# JacdacRotary_26.net
KiCad netlist of a schematic drawn in Altium Designer
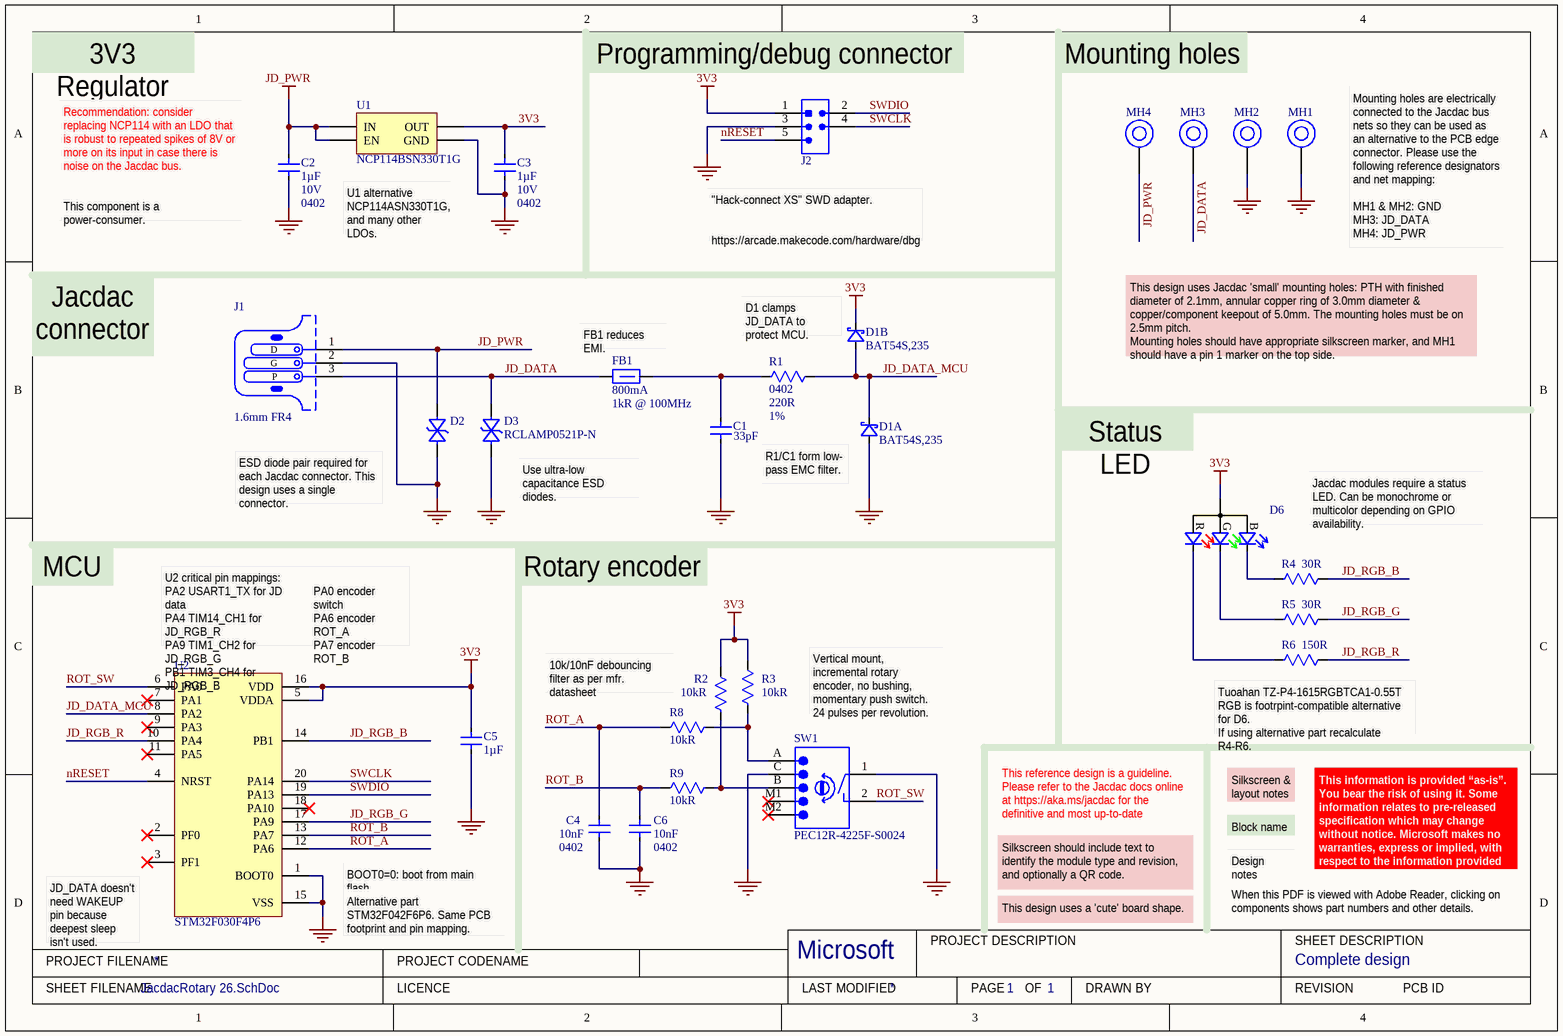
[diagram p0: JacdacRotary 26.SchDoc]

(export (version "E")
  (design (tool "Eeschema 10.0.6"))
  (components
    (comp (ref "C1")
      (value "CL05C330JB5NNNC")
      (footprint "C0402_0.55MM - without outline")
      (description "CAP CER 33PF 50V C0G/NP0 0402")
      (fields
        (field (name "MANUFACTURER") "Samsung")
        (field (name "TOLERANCE") "5%")
        (field (name "CAPACITANCE") "33pF")
      )
      (libsource (lib "Samsung") (part "CL05C330JB5NNNC"))
    )
    (comp (ref "C2")
      (value "CL05A105KP5NNNC")
      (footprint "C0402_0.55MM - without outline")
      (description "CAP CER 1UF 10V X5R 0402")
      (fields
        (field (name "MANUFACTURER") "Samsung")
        (field (name "TOLERANCE") "10%")
        (field (name "CAPACITANCE") "1µF")
        (field (name "VOLTAGE RATING") "10V")
        (field (name "CASE CODE (IMPERIAL)") "0402")
        (field (name "CREATED") "DG")
        (field (name "CHECKED") "?")
      )
      (libsource (lib "Samsung") (part "CL05A105KP5NNNC"))
    )
    (comp (ref "C3")
      (value "CL05A105KP5NNNC")
      (footprint "C0402_0.55MM - without outline")
      (description "CAP CER 1UF 10V X5R 0402")
      (fields
        (field (name "MANUFACTURER") "Samsung")
        (field (name "TOLERANCE") "10%")
        (field (name "CAPACITANCE") "1µF")
        (field (name "VOLTAGE RATING") "10V")
        (field (name "CASE CODE (IMPERIAL)") "0402")
        (field (name "CREATED") "DG")
        (field (name "CHECKED") "?")
      )
      (libsource (lib "Samsung") (part "CL05A105KP5NNNC"))
    )
    (comp (ref "C4")
      (value "~")
      (footprint "C0402_0.55MM - without outline")
      (description "CAP CER 10000PF 16V X7R 0402")
      (fields
        (field (name "MANUFACTURER") "Samsung")
        (field (name "MANUFACTURER PART NUMBER") "CL05B103JO5NNNC")
        (field (name "CAPACITANCE") "10nF")
        (field (name "CASE CODE (IMPERIAL)") "0402")
        (field (name "CREATED BY") "D. Gakure")
        (field (name "CHECKED BY") "?")
      )
      (libsource (lib "Samsung") (part "CL05B103JO5NNNC"))
    )
    (comp (ref "C5")
      (value "CL05A105KP5NNNC")
      (footprint "C0402_0.55MM - without outline")
      (description "CAP CER 1UF 10V X5R 0402")
      (fields
        (field (name "MANUFACTURER") "Samsung")
        (field (name "TOLERANCE") "10%")
        (field (name "CAPACITANCE") "1µF")
        (field (name "CREATED") "DG")
        (field (name "CHECKED") "?")
      )
      (libsource (lib "Samsung") (part "CL05A105KP5NNNC"))
    )
    (comp (ref "C6")
      (value "~")
      (footprint "C0402_0.55MM - without outline")
      (description "CAP CER 10000PF 16V X7R 0402")
      (fields
        (field (name "MANUFACTURER") "Samsung")
        (field (name "MANUFACTURER PART NUMBER") "CL05B103JO5NNNC")
        (field (name "CAPACITANCE") "10nF")
        (field (name "CASE CODE (IMPERIAL)") "0402")
        (field (name "CREATED BY") "D. Gakure")
        (field (name "CHECKED BY") "?")
      )
      (libsource (lib "Samsung") (part "CL05B103JO5NNNC"))
    )
    (comp (ref "D1")
      (value "BAT54S")
      (footprint "NXP-BAT54S-TO-236AB - without outline")
      (description "DIODE ARRAY SCHOTTKY 30V SOT23")
      (fields (field (name "MANUFACTURER") "Nexperia") (field (name "MANUFACTURER PART NUMBER") "BAT54S,235"))
      (libsource (lib "NXP") (part "BAT54S"))
    )
    (comp (ref "D2")
      (value "RCLAMP0521P-N")
      (footprint "TVS 0402 - L")
      (description "Bidirectional 5V (Max) 6V 16V 3.5A (8/20us) 0402 TVS RoHS")
      (fields
        (field (name "MANUFACTURER") "Born Semiconductor")
        (field (name "CREATED BY") "D Gakure")
        (field (name "CHECKED BY") "?")
      )
      (libsource (lib "BornSemiconductor") (part "RCLAMP0521P-N"))
    )
    (comp (ref "D3")
      (value "RCLAMP0521P-N")
      (footprint "TVS 0402 - L")
      (description "Bidirectional 5V (Max) 6V 16V 3.5A (8/20us) 0402 TVS RoHS")
      (fields
        (field (name "MANUFACTURER") "Born Semiconductor")
        (field (name "MANUFACTURER PART NUMBER") "RCLAMP0521P-N")
        (field (name "CREATED BY") "D Gakure")
        (field (name "CHECKED BY") "?")
      )
      (libsource (lib "BornSemiconductor") (part "RCLAMP0521P-N"))
    )
    (comp (ref "D6")
      (value "TZ-P4-1615RGBTCA1-0.55T")
      (footprint "TZ-P4-1615RGBTCA1-0.55T")
      (description "1615 Light Emitting Diodes (LED) RoHS")
      (fields
        (field (name "MANUFACTURER") "TUOZHAN")
        (field (name "CREATED BY") "D. Gakure")
        (field (name "CHECKED BY") "?")
      )
      (libsource (lib "Tuozhan") (part "TZ-P4-1615RGBTCA1-0.55T"))
    )
    (comp (ref "FB1")
      (value "TDK MPZ1608S102ATA00")
      (footprint "TDK MPZ1608 0.8mm - without outline")
      (description "0603 1k@100MHz 0.8A chip")
      (fields
        (field (name "TOLERANCE") "25%")
        (field (name "MANUFACTURER") "TDK")
        (field (name "CURRENT RATING") "800mA")
        (field (name "IMPEDANCE") "1kR @ 100MHz")
      )
      (libsource (lib "TDK") (part "TDK MPZ1608S102ATA00"))
    )
    (comp (ref "J1")
      (value "3 pin JACDAC edge connector")
      (footprint "JACDAC_EDGE_CONNECTOR_NO_TRACES")
      (description "3 pin Jacdac edge connector 1.27mm pitch")
      (fields
        (field (name "MANUFACTURER PART NUMBER") "JACDAC_EDGE_CONNECTOR")
        (field (name "PCB TYPE") "1.6mm FR4")
        (field (name "CHECKED BY") "?")
        (field (name "CREATED BY") "D. Gakure")
      )
      (libsource (lib "generic-con") (part "Jacdac edge connector"))
    )
    (comp (ref "J2")
      (value "Hack Connect Mini 1.27 mm pitch 2-row")
      (footprint "HACK_CONNECT_MINI_5_X_1_27")
      (libsource (lib "HackConnect") (part "HACK_CONNECT_MINI"))
    )
    (comp (ref "MH1")
      (value "MH_5.0MMK_3.0MMC_2.1MMD_PTH")
      (footprint "MH_5.0MMK_3.0MMC_2.1MMD_PTH:MH_5.0MMK_3.0MMC_2.1MMD_PTH")
      (description "Mounting Hole 5.0mm keepout, 3.0mm annualar ring and 2.1mm Drill PTH")
      (libsource (lib "generic") (part "MH_5.0MMK_3.0MMC_2.1MMD_PTH"))
    )
    (comp (ref "MH2")
      (value "MH_5.0MMK_3.0MMC_2.1MMD_PTH")
      (footprint "MH_5.0MMK_3.0MMC_2.1MMD_PTH:MH_5.0MMK_3.0MMC_2.1MMD_PTH")
      (description "Mounting Hole 5.0mm keepout, 3.0mm annualar ring and 2.1mm Drill PTH")
      (libsource (lib "generic") (part "MH_5.0MMK_3.0MMC_2.1MMD_PTH"))
    )
    (comp (ref "MH3")
      (value "MH_5.0MMK_3.0MMC_2.1MMD_PTH")
      (footprint "MH_5.0MMK_3.0MMC_2.1MMD_PTH:MH_5.0MMK_3.0MMC_2.1MMD_PTH")
      (description "Mounting Hole 5.0mm keepout, 3.0mm annualar ring and 2.1mm Drill PTH")
      (libsource (lib "generic") (part "MH_5.0MMK_3.0MMC_2.1MMD_PTH"))
    )
    (comp (ref "MH4")
      (value "MH_5.0MMK_3.0MMC_2.1MMD_PTH")
      (footprint "MH_5.0MMK_3.0MMC_2.1MMD_PTH:MH_5.0MMK_3.0MMC_2.1MMD_PTH")
      (description "Mounting Hole 5.0mm keepout, 3.0mm annualar ring and 2.1mm Drill PTH")
      (libsource (lib "generic") (part "MH_5.0MMK_3.0MMC_2.1MMD_PTH"))
    )
    (comp (ref "R1")
      (value "RC0402FR-07220RL")
      (footprint "R0402 - Without outline")
      (description "RES SMD 220 OHM 1% 1/16W 0402")
      (fields
        (field (name "MANUFACTURER") "Yageo")
        (field (name "CASE CODE (IMPERIAL)") "0402")
        (field (name "RESISTANCE") "220R")
        (field (name "TOLERANCE") "1%")
        (field (name "CREATED") "D.G")
        (field (name "CHECKED") "?")
      )
      (libsource (lib "Yageo") (part "RC0402FR-07220RL"))
    )
    (comp (ref "R2")
      (value "10k")
      (footprint "R0402 - Without outline")
      (description "RES SMD 10K OHM 1% 1/16W 0402")
      (fields
        (field (name "MANUFACTURER") "Yageo")
        (field (name "MANUFACTURER PART NUMBER") "RC0402FR-0710KL")
        (field (name "RESISTANCE") "10kR")
        (field (name "CHECKED") "?")
        (field (name "CREATED") "DG")
      )
      (libsource (lib "Yageo") (part "RC0402FR-0710KL"))
    )
    (comp (ref "R3")
      (value "10k")
      (footprint "R0402 - Without outline")
      (description "RES SMD 10K OHM 1% 1/16W 0402")
      (fields
        (field (name "MANUFACTURER") "Yageo")
        (field (name "MANUFACTURER PART NUMBER") "RC0402FR-0710KL")
        (field (name "RESISTANCE") "10kR")
        (field (name "CHECKED") "?")
        (field (name "CREATED") "DG")
      )
      (libsource (lib "Yageo") (part "RC0402FR-0710KL"))
    )
    (comp (ref "R4")
      (value "RC0402FR-0730RL")
      (footprint "R0402 - Without outline")
      (description "RES SMD 30 OHM 1% 1/16W 0402")
      (fields
        (field (name "MANUFACTURER") "Yageo")
        (field (name "RESISTANCE") "30R")
        (field (name "TOLERANCE") "1%")
        (field (name "CREATED BY") "D. Gakure")
        (field (name "CHECKED BY") "?")
      )
      (libsource (lib "Yageo") (part "RC0402FR-0730RL"))
    )
    (comp (ref "R5")
      (value "RC0402FR-0730RL")
      (footprint "R0402 - Without outline")
      (description "RES SMD 30 OHM 1% 1/16W 0402")
      (fields
        (field (name "MANUFACTURER") "Yageo")
        (field (name "RESISTANCE") "30R")
        (field (name "TOLERANCE") "1%")
        (field (name "CREATED BY") "D. Gakure")
        (field (name "CHECKED BY") "?")
      )
      (libsource (lib "Yageo") (part "RC0402FR-0730RL"))
    )
    (comp (ref "R6")
      (value "RC0402FR-07150RL")
      (footprint "R0402 - Without outline")
      (description "RES SMD 150 OHM 1% 1/16W 0402")
      (fields
        (field (name "MANUFACTURER") "Yageo")
        (field (name "RESISTANCE") "150R")
        (field (name "TOLERANCE") "1%")
        (field (name "CREATED BY") "D. Gakure")
        (field (name "CHECKED BY") "?")
      )
      (libsource (lib "Yageo") (part "RC0402FR-07150RL"))
    )
    (comp (ref "R8")
      (value "10k")
      (footprint "R0402 - Without outline")
      (description "RES SMD 10K OHM 1% 1/16W 0402")
      (fields
        (field (name "MANUFACTURER") "Yageo")
        (field (name "MANUFACTURER PART NUMBER") "RC0402FR-0710KL")
        (field (name "RESISTANCE") "10kR")
        (field (name "CHECKED") "?")
        (field (name "CREATED") "DG")
      )
      (libsource (lib "Yageo") (part "RC0402FR-0710KL"))
    )
    (comp (ref "R9")
      (value "10k")
      (footprint "R0402 - Without outline")
      (description "RES SMD 10K OHM 1% 1/16W 0402")
      (fields
        (field (name "MANUFACTURER") "Yageo")
        (field (name "MANUFACTURER PART NUMBER") "RC0402FR-0710KL")
        (field (name "RESISTANCE") "10kR")
        (field (name "CHECKED") "?")
        (field (name "CREATED") "DG")
      )
      (libsource (lib "Yageo") (part "RC0402FR-0710KL"))
    )
    (comp (ref "SW1")
      (value "PEC12R-4225F-S0024")
      (footprint "PEC12R-4225F-S0024 -Standoff 2.4mm- Slotted MH")
      (description "Rotary Encoder Mechanical 24 Quadrature (Incremental) Vertical")
      (fields
        (field (name "MANUFACTURER") "Bourns")
        (field (name "MANUFACTURER PART NUMBER") "PEC12R-4225F-S0024")
        (field (name "CREATED BY") "D. Gakure")
        (field (name "CHECKED BY") "?")
      )
      (libsource (lib "Bourns") (part "PEC12R-4225F-S0024"))
    )
    (comp (ref "U1")
      (value "LDO 3.3V/300 mA")
      (footprint "ON_SEMI-SOT23-5 - without outline")
      (description "CMOS Low Dropout Regulator (LDO), 300 mA 3.3V, Non-Active Discharge, TSOP5")
      (fields
        (field (name "MANUFACTURER") "ON Semiconductor")
        (field (name "MANUFACTURER PART NUMBER") "NCP114BSN330T1G")
      )
      (libsource (lib "OnSemiconductor") (part "NCP114BSN330T1G"))
    )
    (comp (ref "U2")
      (value "STM32F030F4P6")
      (footprint "20-TSSOP - without outline")
      (description "ARM Cortex-M0 STM32F0 Microcontroller IC 32-Bit 48MHz 16KB (16K x 8) FLASH")
      (fields
        (field (name "MANUFACTURER") "STMicroelectronics")
        (field (name "MANUFACTURER PART NUMBER") "STM32F030F4P6")
        (field (name "CREATED") "DG")
        (field (name "CHECKED") "?")
        (field (name "CREATED BY") "D. Gakure")
        (field (name "CHECKED BY") "?")
      )
      (libsource (lib "ST") (part "ST STM32F030F4P6"))
    )
  )
  (nets
    (net (code "1") (name "/JD_DATA") (class "Default")
      (node (ref "D3") (pin "1") (pinfunction "K_1") (pintype "passive"))
      (node (ref "FB1") (pin "1") (pinfunction "1_1") (pintype "passive"))
      (node (ref "J1") (pin "3") (pinfunction "P_3") (pintype "passive"))
      (node (ref "MH3") (pin "1") (pinfunction "1_1") (pintype "passive"))
    )
    (net (code "2") (name "/JD_DATA_MCU") (class "Default")
      (node (ref "D1") (pin "3") (pinfunction "K_3") (pintype "passive"))
      (node (ref "R1") (pin "1") (pinfunction "1_1") (pintype "passive"))
      (node (ref "U2") (pin "8") (pinfunction "PA2_8") (pintype "passive"))
    )
    (net (code "3") (name "/JD_RGB_B") (class "Default")
      (node (ref "R4") (pin "2") (pinfunction "2_2") (pintype "passive"))
      (node (ref "U2") (pin "14") (pinfunction "PB1_14") (pintype "passive"))
    )
    (net (code "4") (name "/JD_RGB_G") (class "Default")
      (node (ref "R5") (pin "2") (pinfunction "2_2") (pintype "passive"))
      (node (ref "U2") (pin "17") (pinfunction "PA9_17") (pintype "passive"))
    )
    (net (code "5") (name "/JD_RGB_R") (class "Default")
      (node (ref "R6") (pin "2") (pinfunction "2_2") (pintype "passive"))
      (node (ref "U2") (pin "10") (pinfunction "PA4_10") (pintype "passive"))
    )
    (net (code "6") (name "/ROT_A") (class "Default")
      (node (ref "C4") (pin "2") (pinfunction "2_2") (pintype "passive"))
      (node (ref "R8") (pin "1") (pinfunction "1_1") (pintype "passive"))
      (node (ref "U2") (pin "12") (pinfunction "PA6_12") (pintype "passive"))
    )
    (net (code "7") (name "/ROT_B") (class "Default")
      (node (ref "C6") (pin "2") (pinfunction "2_2") (pintype "passive"))
      (node (ref "R9") (pin "1") (pinfunction "1_1") (pintype "passive"))
      (node (ref "U2") (pin "13") (pinfunction "PA7_13") (pintype "passive"))
    )
    (net (code "8") (name "/ROT_SW") (class "Default")
      (node (ref "SW1") (pin "2") (pinfunction "2_2") (pintype "passive"))
      (node (ref "U2") (pin "6") (pinfunction "PA0_6") (pintype "passive"))
    )
    (net (code "9") (name "/SWCLK") (class "Default")
      (node (ref "J2") (pin "4") (pinfunction "SWCLK_4") (pintype "passive"))
      (node (ref "U2") (pin "20") (pinfunction "PA14_20") (pintype "passive"))
    )
    (net (code "10") (name "/SWDIO") (class "Default")
      (node (ref "J2") (pin "2") (pinfunction "SWDIO_2") (pintype "passive"))
      (node (ref "U2") (pin "19") (pinfunction "PA13_19") (pintype "passive"))
    )
    (net (code "11") (name "/nRESET") (class "Default")
      (node (ref "J2") (pin "5") (pinfunction "RESET_5") (pintype "passive"))
      (node (ref "U2") (pin "4") (pinfunction "NRST_4") (pintype "passive"))
    )
    (net (code "12") (name "3V3") (class "Default")
      (node (ref "C3") (pin "2") (pinfunction "2_2") (pintype "passive"))
      (node (ref "C5") (pin "2") (pinfunction "2_2") (pintype "passive"))
      (node (ref "D1") (pin "2") (pinfunction "K_2") (pintype "passive"))
      (node (ref "D6") (pin "1") (pinfunction "A_1") (pintype "passive"))
      (node (ref "J2") (pin "1") (pinfunction "VCC_1") (pintype "passive"))
      (node (ref "R2") (pin "1") (pinfunction "1_1") (pintype "passive"))
      (node (ref "R3") (pin "1") (pinfunction "1_1") (pintype "passive"))
      (node (ref "U1") (pin "5") (pinfunction "OUT_5") (pintype "passive"))
      (node (ref "U2") (pin "16") (pinfunction "VDD_16") (pintype "power_in"))
      (node (ref "U2") (pin "5") (pinfunction "VDDA_5") (pintype "power_in"))
    )
    (net (code "13") (name "GND") (class "Default")
      (node (ref "C1") (pin "1") (pinfunction "1_1") (pintype "passive"))
      (node (ref "C2") (pin "1") (pinfunction "1_1") (pintype "passive"))
      (node (ref "C3") (pin "1") (pinfunction "1_1") (pintype "passive"))
      (node (ref "C4") (pin "1") (pinfunction "1_1") (pintype "passive"))
      (node (ref "C5") (pin "1") (pinfunction "1_1") (pintype "passive"))
      (node (ref "C6") (pin "1") (pinfunction "1_1") (pintype "passive"))
      (node (ref "D1") (pin "1") (pinfunction "A_1") (pintype "passive"))
      (node (ref "D2") (pin "2") (pinfunction "A_2") (pintype "passive"))
      (node (ref "D3") (pin "2") (pinfunction "A_2") (pintype "passive"))
      (node (ref "J1") (pin "2") (pinfunction "G_2") (pintype "passive"))
      (node (ref "J2") (pin "3") (pinfunction "GND_3") (pintype "passive"))
      (node (ref "MH1") (pin "1") (pinfunction "1_1") (pintype "passive"))
      (node (ref "MH2") (pin "1") (pinfunction "1_1") (pintype "passive"))
      (node (ref "SW1") (pin "1") (pinfunction "1_1") (pintype "passive"))
      (node (ref "SW1") (pin "C") (pinfunction "C_C") (pintype "passive"))
      (node (ref "U1") (pin "2") (pinfunction "GND_2") (pintype "passive"))
      (node (ref "U2") (pin "1") (pinfunction "BOOT0_1") (pintype "passive"))
      (node (ref "U2") (pin "15") (pinfunction "VSS_15") (pintype "power_in"))
    )
    (net (code "14") (name "JD_PWR") (class "Default")
      (node (ref "C2") (pin "2") (pinfunction "2_2") (pintype "passive"))
      (node (ref "D2") (pin "1") (pinfunction "K_1") (pintype "passive"))
      (node (ref "J1") (pin "1") (pinfunction "D_1") (pintype "passive"))
      (node (ref "MH4") (pin "1") (pinfunction "1_1") (pintype "passive"))
      (node (ref "U1") (pin "1") (pinfunction "IN_1") (pintype "passive"))
      (node (ref "U1") (pin "3") (pinfunction "EN_3") (pintype "passive"))
    )
    (net (code "15") (name "Net-(C1-Pad2)") (class "Default")
      (node (ref "C1") (pin "2") (pinfunction "2_2") (pintype "passive"))
      (node (ref "FB1") (pin "2") (pinfunction "2_2") (pintype "passive"))
      (node (ref "R1") (pin "2") (pinfunction "2_2") (pintype "passive"))
    )
    (net (code "16") (name "Net-(D6-B)") (class "Default")
      (node (ref "D6") (pin "4") (pinfunction "B_4") (pintype "passive"))
      (node (ref "R4") (pin "1") (pinfunction "1_1") (pintype "passive"))
    )
    (net (code "17") (name "Net-(D6-G)") (class "Default")
      (node (ref "D6") (pin "3") (pinfunction "G_3") (pintype "passive"))
      (node (ref "R5") (pin "1") (pinfunction "1_1") (pintype "passive"))
    )
    (net (code "18") (name "Net-(D6-R)") (class "Default")
      (node (ref "D6") (pin "2") (pinfunction "R_2") (pintype "passive"))
      (node (ref "R6") (pin "1") (pinfunction "1_1") (pintype "passive"))
    )
    (net (code "19") (name "Net-(R2-Pad2)") (class "Default")
      (node (ref "R2") (pin "2") (pinfunction "2_2") (pintype "passive"))
      (node (ref "R9") (pin "2") (pinfunction "2_2") (pintype "passive"))
      (node (ref "SW1") (pin "B") (pinfunction "B_B") (pintype "passive"))
    )
    (net (code "20") (name "Net-(R3-Pad2)") (class "Default")
      (node (ref "R3") (pin "2") (pinfunction "2_2") (pintype "passive"))
      (node (ref "R8") (pin "2") (pinfunction "2_2") (pintype "passive"))
      (node (ref "SW1") (pin "A") (pinfunction "A_A") (pintype "passive"))
    )
    (net (code "21") (name "unconnected-(SW1-PadM1)") (class "Default")
      (node (ref "SW1") (pin "M1") (pinfunction "M1_M1") (pintype "passive+no_connect"))
    )
    (net (code "22") (name "unconnected-(SW1-PadM2)") (class "Default")
      (node (ref "SW1") (pin "M2") (pinfunction "M2_M2") (pintype "passive+no_connect"))
    )
    (net (code "23") (name "unconnected-(U2-PA1-Pad7)") (class "Default")
      (node (ref "U2") (pin "7") (pinfunction "PA1_7") (pintype "passive+no_connect"))
    )
    (net (code "24") (name "unconnected-(U2-PA3-Pad9)") (class "Default")
      (node (ref "U2") (pin "9") (pinfunction "PA3_9") (pintype "passive+no_connect"))
    )
    (net (code "25") (name "unconnected-(U2-PA5-Pad11)") (class "Default")
      (node (ref "U2") (pin "11") (pinfunction "PA5_11") (pintype "passive+no_connect"))
    )
    (net (code "26") (name "unconnected-(U2-PA10-Pad18)") (class "Default")
      (node (ref "U2") (pin "18") (pinfunction "PA10_18") (pintype "passive+no_connect"))
    )
    (net (code "27") (name "unconnected-(U2-PF0-Pad2)") (class "Default")
      (node (ref "U2") (pin "2") (pinfunction "PF0_2") (pintype "passive+no_connect"))
    )
    (net (code "28") (name "unconnected-(U2-PF1-Pad3)") (class "Default")
      (node (ref "U2") (pin "3") (pinfunction "PF1_3") (pintype "passive+no_connect"))
    )
  )
)
